# 03-MCU.net
KiCad netlist of a schematic drawn in Altium Designer
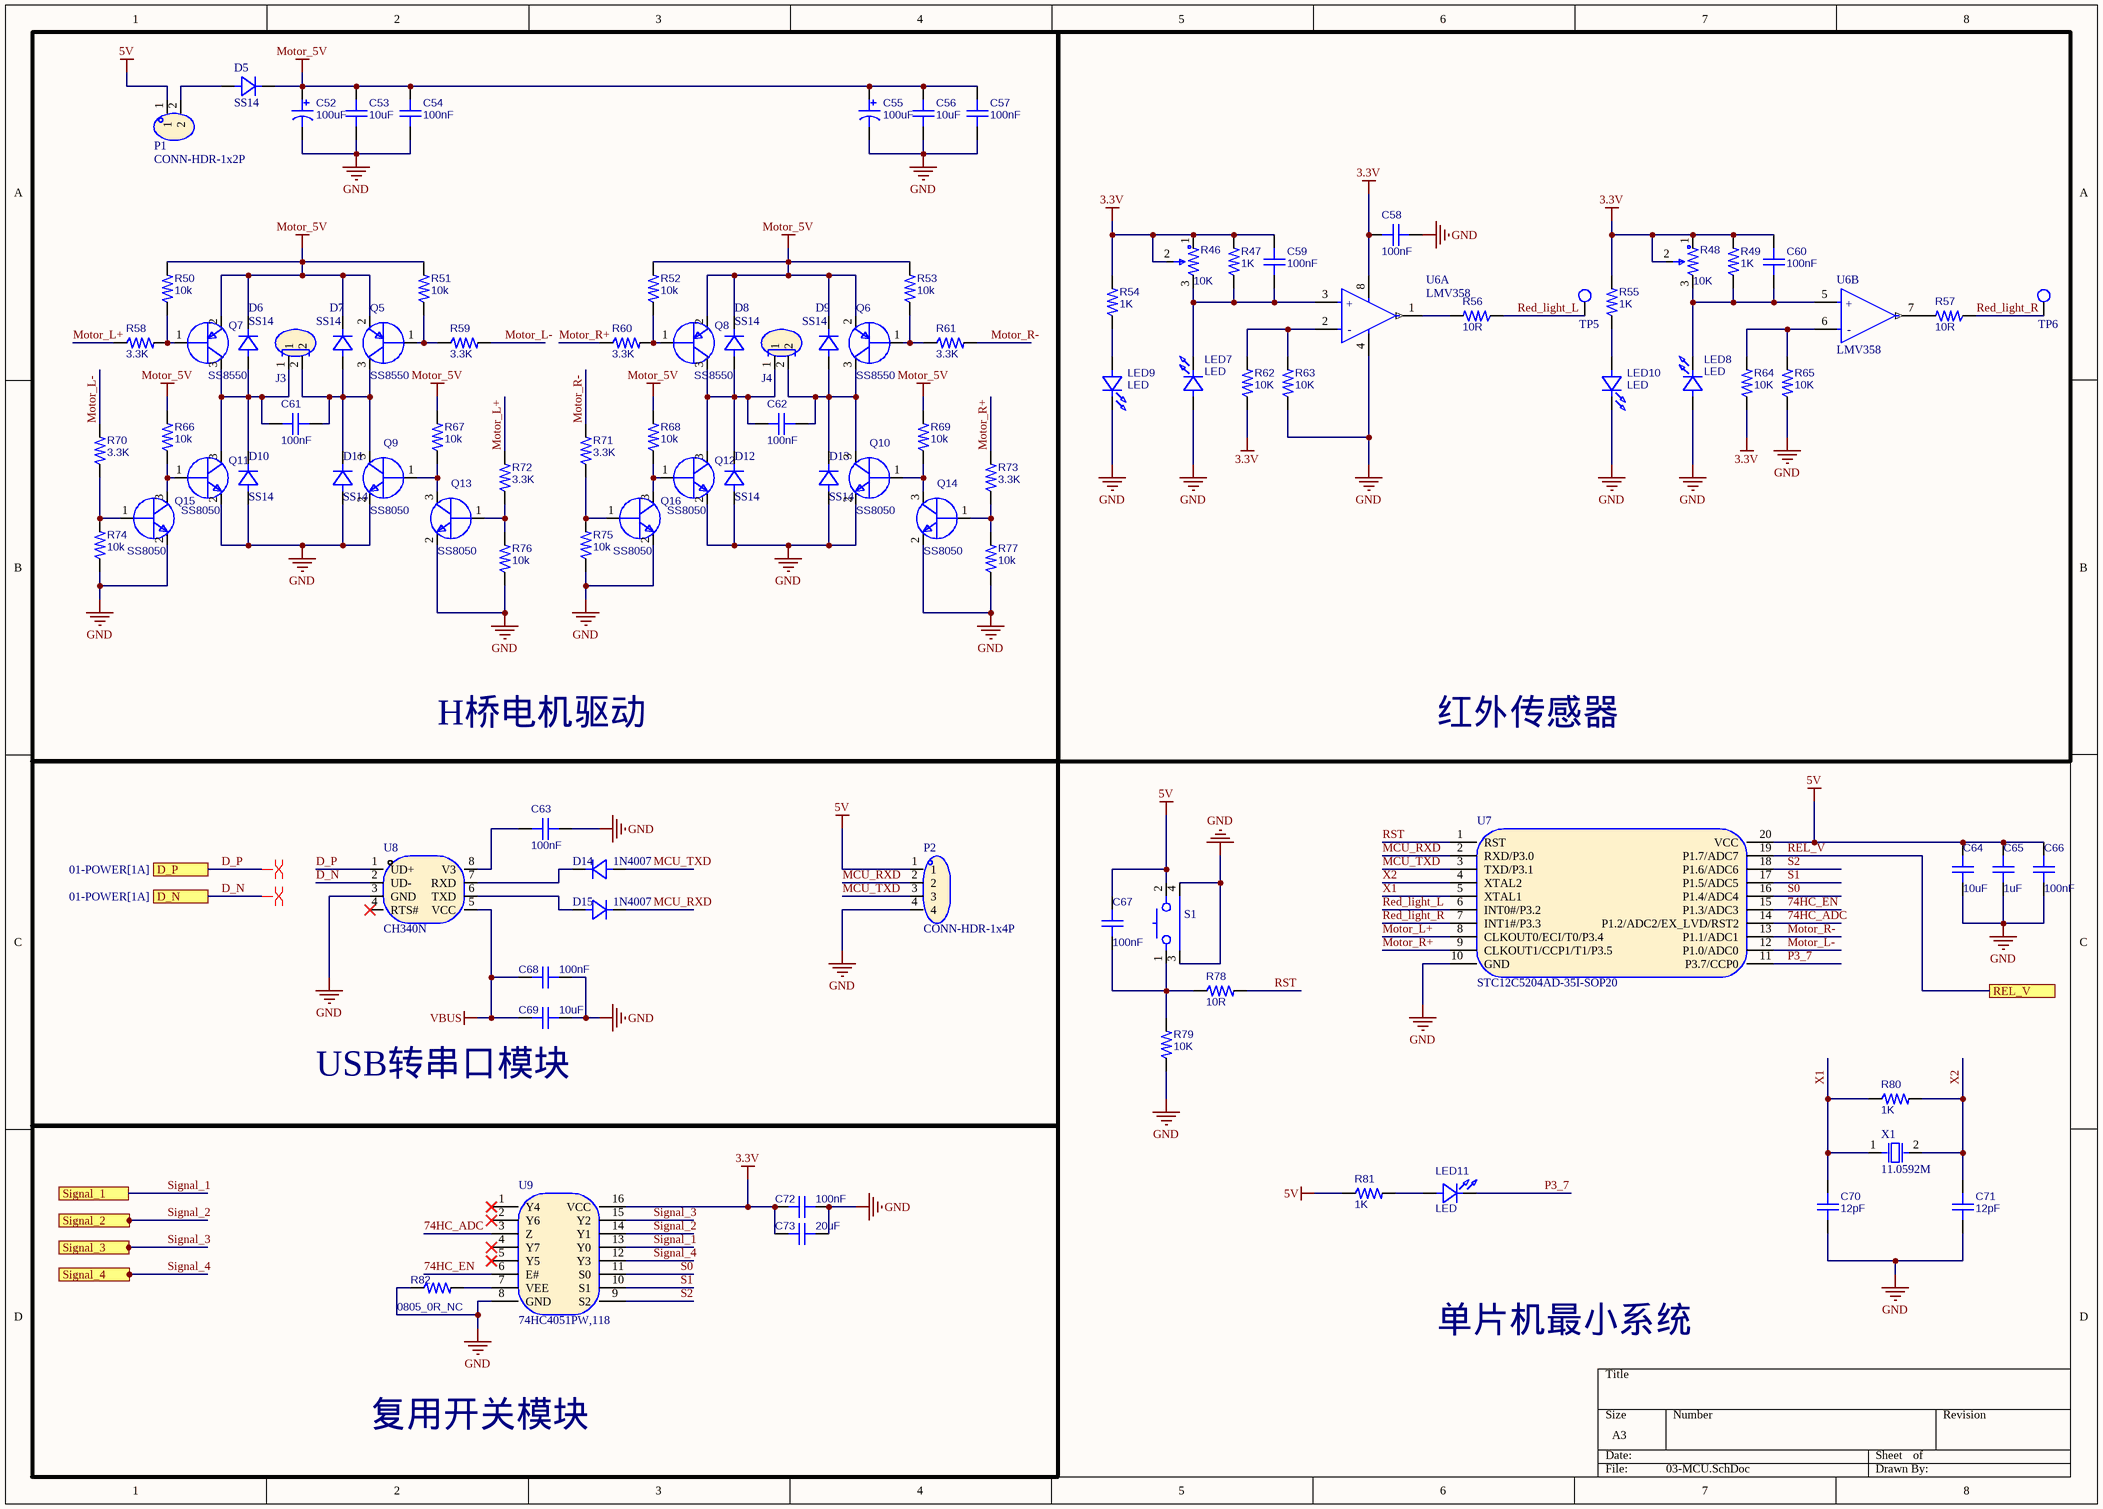
[diagram p0: 03-MCU.SchDoc]

(export (version "E")
  (design (tool "Eeschema 10.0.6"))
  (components
    (comp (ref "C52")
      (value "100uF")
      (footprint "CAPA-TH-5020-P2.0")
      (description "电解电容")
      (fields
        (field (name "BOM_MANUFACTURER PART") "普通黑色470UF 50V")
        (field (name "BOM_SUPPLIER PART") "C34642")
      )
      (libsource (lib "声源跟踪小车原理图库") (part "CAPA"))
    )
    (comp (ref "C53")
      (value "10uF")
      (footprint "CAP-SMD-0603")
      (description "贴片电容")
      (fields
        (field (name "BOM_MANUFACTURER PART") "CL03A104KQ3NNNC")
        (field (name "BOM_SUPPLIER PART") "C160831")
        (field (name "CONTRIBUTOR") "LCSC")
      )
      (libsource (lib "声源跟踪小车原理图库") (part "CAP"))
    )
    (comp (ref "C54")
      (value "100nF")
      (footprint "CAP-SMD-0603")
      (description "贴片电容")
      (fields
        (field (name "BOM_MANUFACTURER PART") "CL03A104KQ3NNNC")
        (field (name "BOM_SUPPLIER PART") "C160831")
        (field (name "CONTRIBUTOR") "LCSC")
      )
      (libsource (lib "声源跟踪小车原理图库") (part "CAP"))
    )
    (comp (ref "C55")
      (value "100uF")
      (footprint "CAPA-TH-5020-P2.0")
      (description "电解电容")
      (fields
        (field (name "BOM_MANUFACTURER PART") "普通黑色470UF 50V")
        (field (name "BOM_SUPPLIER PART") "C34642")
      )
      (libsource (lib "声源跟踪小车原理图库") (part "CAPA"))
    )
    (comp (ref "C56")
      (value "10uF")
      (footprint "CAP-SMD-0603")
      (description "贴片电容")
      (fields
        (field (name "BOM_MANUFACTURER PART") "CL03A104KQ3NNNC")
        (field (name "BOM_SUPPLIER PART") "C160831")
        (field (name "CONTRIBUTOR") "LCSC")
      )
      (libsource (lib "声源跟踪小车原理图库") (part "CAP"))
    )
    (comp (ref "C57")
      (value "100nF")
      (footprint "CAP-SMD-0603")
      (description "贴片电容")
      (fields
        (field (name "BOM_MANUFACTURER PART") "CL03A104KQ3NNNC")
        (field (name "BOM_SUPPLIER PART") "C160831")
        (field (name "CONTRIBUTOR") "LCSC")
      )
      (libsource (lib "声源跟踪小车原理图库") (part "CAP"))
    )
    (comp (ref "C58")
      (value "100nF")
      (footprint "CAP-SMD-0603")
      (description "贴片电容")
      (fields
        (field (name "BOM_MANUFACTURER PART") "CL03A104KQ3NNNC")
        (field (name "BOM_SUPPLIER PART") "C160831")
        (field (name "CONTRIBUTOR") "LCSC")
      )
      (libsource (lib "声源跟踪小车原理图库") (part "CAP"))
    )
    (comp (ref "C59")
      (value "100nF")
      (footprint "CAP-SMD-0603")
      (description "贴片电容")
      (fields
        (field (name "BOM_MANUFACTURER PART") "CL03A104KQ3NNNC")
        (field (name "BOM_SUPPLIER PART") "C160831")
        (field (name "CONTRIBUTOR") "LCSC")
      )
      (libsource (lib "声源跟踪小车原理图库") (part "CAP"))
    )
    (comp (ref "C60")
      (value "100nF")
      (footprint "CAP-SMD-0603")
      (description "贴片电容")
      (fields
        (field (name "BOM_MANUFACTURER PART") "CL03A104KQ3NNNC")
        (field (name "BOM_SUPPLIER PART") "C160831")
        (field (name "CONTRIBUTOR") "LCSC")
      )
      (libsource (lib "声源跟踪小车原理图库") (part "CAP"))
    )
    (comp (ref "C61")
      (value "100nF")
      (footprint "CAP-SMD-0603")
      (description "贴片电容")
      (fields
        (field (name "BOM_MANUFACTURER PART") "CL03A104KQ3NNNC")
        (field (name "BOM_SUPPLIER PART") "C160831")
        (field (name "CONTRIBUTOR") "LCSC")
      )
      (libsource (lib "声源跟踪小车原理图库") (part "CAP"))
    )
    (comp (ref "C62")
      (value "100nF")
      (footprint "CAP-SMD-0603")
      (description "贴片电容")
      (fields
        (field (name "BOM_MANUFACTURER PART") "CL03A104KQ3NNNC")
        (field (name "BOM_SUPPLIER PART") "C160831")
        (field (name "CONTRIBUTOR") "LCSC")
      )
      (libsource (lib "声源跟踪小车原理图库") (part "CAP"))
    )
    (comp (ref "C63")
      (value "100nF")
      (footprint "CAP-SMD-0603")
      (description "贴片电容")
      (fields
        (field (name "BOM_MANUFACTURER PART") "CL03A104KQ3NNNC")
        (field (name "BOM_SUPPLIER PART") "C160831")
        (field (name "CONTRIBUTOR") "LCSC")
      )
      (libsource (lib "声源跟踪小车原理图库") (part "CAP"))
    )
    (comp (ref "C64")
      (value "10uF")
      (footprint "CAP-SMD-0603")
      (description "贴片电容")
      (fields
        (field (name "BOM_MANUFACTURER PART") "CL03A104KQ3NNNC")
        (field (name "BOM_SUPPLIER PART") "C160831")
        (field (name "CONTRIBUTOR") "LCSC")
      )
      (libsource (lib "声源跟踪小车原理图库") (part "CAP"))
    )
    (comp (ref "C65")
      (value "1uF")
      (footprint "CAP-SMD-0603")
      (description "贴片电容")
      (fields
        (field (name "BOM_MANUFACTURER PART") "CL03A104KQ3NNNC")
        (field (name "BOM_SUPPLIER PART") "C160831")
        (field (name "CONTRIBUTOR") "LCSC")
      )
      (libsource (lib "声源跟踪小车原理图库") (part "CAP"))
    )
    (comp (ref "C66")
      (value "100nF")
      (footprint "CAP-SMD-0603")
      (description "贴片电容")
      (fields
        (field (name "BOM_MANUFACTURER PART") "CL03A104KQ3NNNC")
        (field (name "BOM_SUPPLIER PART") "C160831")
        (field (name "CONTRIBUTOR") "LCSC")
      )
      (libsource (lib "声源跟踪小车原理图库") (part "CAP"))
    )
    (comp (ref "C67")
      (value "100nF")
      (footprint "CAP-SMD-0603")
      (description "贴片电容")
      (fields
        (field (name "BOM_MANUFACTURER PART") "CL03A104KQ3NNNC")
        (field (name "BOM_SUPPLIER PART") "C160831")
        (field (name "CONTRIBUTOR") "LCSC")
      )
      (libsource (lib "声源跟踪小车原理图库") (part "CAP"))
    )
    (comp (ref "C68")
      (value "100nF")
      (footprint "CAP-SMD-0603")
      (description "贴片电容")
      (fields
        (field (name "BOM_MANUFACTURER PART") "CL03A104KQ3NNNC")
        (field (name "BOM_SUPPLIER PART") "C160831")
        (field (name "CONTRIBUTOR") "LCSC")
      )
      (libsource (lib "声源跟踪小车原理图库") (part "CAP"))
    )
    (comp (ref "C69")
      (value "10uF")
      (footprint "CAP-SMD-0603")
      (description "贴片电容")
      (fields
        (field (name "BOM_MANUFACTURER PART") "CL03A104KQ3NNNC")
        (field (name "BOM_SUPPLIER PART") "C160831")
        (field (name "CONTRIBUTOR") "LCSC")
      )
      (libsource (lib "声源跟踪小车原理图库") (part "CAP"))
    )
    (comp (ref "C70")
      (value "12pF")
      (footprint "CAP-SMD-0603")
      (description "贴片电容")
      (fields
        (field (name "BOM_MANUFACTURER PART") "CL03A104KQ3NNNC")
        (field (name "BOM_SUPPLIER PART") "C160831")
        (field (name "CONTRIBUTOR") "LCSC")
      )
      (libsource (lib "声源跟踪小车原理图库") (part "CAP"))
    )
    (comp (ref "C71")
      (value "12pF")
      (footprint "CAP-SMD-0603")
      (description "贴片电容")
      (fields
        (field (name "BOM_MANUFACTURER PART") "CL03A104KQ3NNNC")
        (field (name "BOM_SUPPLIER PART") "C160831")
        (field (name "CONTRIBUTOR") "LCSC")
      )
      (libsource (lib "声源跟踪小车原理图库") (part "CAP"))
    )
    (comp (ref "C72")
      (value "100nF")
      (footprint "CAP-SMD-0603")
      (description "贴片电容")
      (fields
        (field (name "BOM_MANUFACTURER PART") "CL03A104KQ3NNNC")
        (field (name "BOM_SUPPLIER PART") "C160831")
        (field (name "CONTRIBUTOR") "LCSC")
      )
      (libsource (lib "声源跟踪小车原理图库") (part "CAP"))
    )
    (comp (ref "C73")
      (value "20uF")
      (footprint "CAP-SMD-0603")
      (description "贴片电容")
      (fields
        (field (name "BOM_MANUFACTURER PART") "CL03A104KQ3NNNC")
        (field (name "BOM_SUPPLIER PART") "C160831")
        (field (name "CONTRIBUTOR") "LCSC")
      )
      (libsource (lib "声源跟踪小车原理图库") (part "CAP"))
    )
    (comp (ref "D5")
      (value "SS14")
      (footprint "SOD-123-P3.4")
      (description "二极管1N4148W")
      (fields (field (name "MANUFACTURER") "PSI(宝力芯)") (field (name "MANUFACTURER PART") "1N4148W"))
      (libsource (lib "声源跟踪小车原理图库") (part "Diode"))
    )
    (comp (ref "D6")
      (value "SS14")
      (footprint "SOD-123-P3.4")
      (description "二极管1N4148W")
      (fields (field (name "MANUFACTURER") "PSI(宝力芯)") (field (name "MANUFACTURER PART") "1N4148W"))
      (libsource (lib "声源跟踪小车原理图库") (part "Diode"))
    )
    (comp (ref "D7")
      (value "SS14")
      (footprint "SOD-123-P3.4")
      (description "二极管1N4148W")
      (fields (field (name "MANUFACTURER") "PSI(宝力芯)") (field (name "MANUFACTURER PART") "1N4148W"))
      (libsource (lib "声源跟踪小车原理图库") (part "Diode"))
    )
    (comp (ref "D8")
      (value "SS14")
      (footprint "SOD-123-P3.4")
      (description "二极管1N4148W")
      (fields (field (name "MANUFACTURER") "PSI(宝力芯)") (field (name "MANUFACTURER PART") "1N4148W"))
      (libsource (lib "声源跟踪小车原理图库") (part "Diode"))
    )
    (comp (ref "D9")
      (value "SS14")
      (footprint "SOD-123-P3.4")
      (description "二极管1N4148W")
      (fields (field (name "MANUFACTURER") "PSI(宝力芯)") (field (name "MANUFACTURER PART") "1N4148W"))
      (libsource (lib "声源跟踪小车原理图库") (part "Diode"))
    )
    (comp (ref "D10")
      (value "SS14")
      (footprint "SOD-123-P3.4")
      (description "二极管1N4148W")
      (fields (field (name "MANUFACTURER") "PSI(宝力芯)") (field (name "MANUFACTURER PART") "1N4148W"))
      (libsource (lib "声源跟踪小车原理图库") (part "Diode"))
    )
    (comp (ref "D11")
      (value "SS14")
      (footprint "SOD-123-P3.4")
      (description "二极管1N4148W")
      (fields (field (name "MANUFACTURER") "PSI(宝力芯)") (field (name "MANUFACTURER PART") "1N4148W"))
      (libsource (lib "声源跟踪小车原理图库") (part "Diode"))
    )
    (comp (ref "D12")
      (value "SS14")
      (footprint "SOD-123-P3.4")
      (description "二极管1N4148W")
      (fields (field (name "MANUFACTURER") "PSI(宝力芯)") (field (name "MANUFACTURER PART") "1N4148W"))
      (libsource (lib "声源跟踪小车原理图库") (part "Diode"))
    )
    (comp (ref "D13")
      (value "SS14")
      (footprint "SOD-123-P3.4")
      (description "二极管1N4148W")
      (fields (field (name "MANUFACTURER") "PSI(宝力芯)") (field (name "MANUFACTURER PART") "1N4148W"))
      (libsource (lib "声源跟踪小车原理图库") (part "Diode"))
    )
    (comp (ref "D14")
      (value "1N4007")
      (footprint "SOD-123-P3.4")
      (description "二极管1N4148W")
      (fields (field (name "MANUFACTURER") "PSI(宝力芯)") (field (name "MANUFACTURER PART") "1N4148W"))
      (libsource (lib "声源跟踪小车原理图库") (part "Diode"))
    )
    (comp (ref "D15")
      (value "1N4007")
      (footprint "SOD-123-P3.4")
      (description "二极管1N4148W")
      (fields (field (name "MANUFACTURER") "PSI(宝力芯)") (field (name "MANUFACTURER PART") "1N4148W"))
      (libsource (lib "声源跟踪小车原理图库") (part "Diode"))
    )
    (comp (ref "J3")
      (value "CONN-2P")
      (footprint "CONN-TH-CDS-1x2P-P2.54")
      (description "连接插座2pin")
      (fields (field (name "MANUFACTURER") "KEFA(科发)") (field (name "MANUFACTURER PART") "KF301-5.0-2P"))
      (libsource (lib "声源跟踪小车原理图库") (part "CONN-2P"))
    )
    (comp (ref "J4")
      (value "CONN-2P")
      (footprint "CONN-TH-CDS-1x2P-P2.54")
      (description "连接插座2pin")
      (fields (field (name "MANUFACTURER") "KEFA(科发)") (field (name "MANUFACTURER PART") "KF301-5.0-2P"))
      (libsource (lib "声源跟踪小车原理图库") (part "CONN-2P"))
    )
    (comp (ref "LED7")
      (value "LED")
      (footprint "LED-TH-D5.0-P2.54")
      (description "LED灯,发光二极管")
      (fields
        (field (name "BOM_SUPPLIER PART") "C434447")
        (field (name "BOM_MANUFACTURER PART") "SZYY0402B")
        (field (name "CONTRIBUTOR") "LCSC")
      )
      (libsource (lib "声源跟踪小车原理图库") (part "LED"))
    )
    (comp (ref "LED8")
      (value "LED")
      (footprint "LED-TH-D5.0-P2.54")
      (description "LED灯,发光二极管")
      (fields
        (field (name "BOM_SUPPLIER PART") "C434447")
        (field (name "BOM_MANUFACTURER PART") "SZYY0402B")
        (field (name "CONTRIBUTOR") "LCSC")
      )
      (libsource (lib "声源跟踪小车原理图库") (part "LED"))
    )
    (comp (ref "LED9")
      (value "LED")
      (footprint "LED-TH-D5.0-P2.54")
      (description "LED灯,发光二极管")
      (fields
        (field (name "BOM_SUPPLIER PART") "C434447")
        (field (name "BOM_MANUFACTURER PART") "SZYY0402B")
        (field (name "CONTRIBUTOR") "LCSC")
      )
      (libsource (lib "声源跟踪小车原理图库") (part "LED"))
    )
    (comp (ref "LED10")
      (value "LED")
      (footprint "LED-TH-D5.0-P2.54")
      (description "LED灯,发光二极管")
      (fields
        (field (name "BOM_SUPPLIER PART") "C434447")
        (field (name "BOM_MANUFACTURER PART") "SZYY0402B")
        (field (name "CONTRIBUTOR") "LCSC")
      )
      (libsource (lib "声源跟踪小车原理图库") (part "LED"))
    )
    (comp (ref "LED11")
      (value "LED")
      (footprint "LED-SMD-0805")
      (description "LED灯,发光二极管")
      (fields
        (field (name "BOM_SUPPLIER PART") "C434447")
        (field (name "BOM_MANUFACTURER PART") "SZYY0402B")
        (field (name "CONTRIBUTOR") "LCSC")
      )
      (libsource (lib "声源跟踪小车原理图库") (part "LED"))
    )
    (comp (ref "P1")
      (value "CONN-HDR-1x2P")
      (footprint "CONN-TH-1X2P-P2.54")
      (description "排针1*2pin")
      (fields
        (field (name "MANUFACTURER") "kinghelm(金航标)")
        (field (name "MANUFACTURER PART") "KH-2.54PH180-1X2P-L11.5")
      )
      (libsource (lib "声源跟踪小车原理图库") (part "CONN-HDR-1x2P"))
    )
    (comp (ref "P2")
      (value "CONN-HDR-1x4P")
      (footprint "CONN-TH-1X4P-P2.54")
      (description "排针1*4pin")
      (fields
        (field (name "MANUFACTURER") "Wcon(维峰电子)")
        (field (name "MANUFACTURER PART") "1125-1104G0S116C001")
      )
      (libsource (lib "声源跟踪小车原理图库") (part "CONN-HDR-1x4P"))
    )
    (comp (ref "Q5")
      (value "SS8550")
      (footprint "SOT-23-3-LP2.28-P1.91")
      (description "贴片PNP三极管")
      (fields
        (field (name "BOM_SUPPLIER PART") "C2891799")
        (field (name "BOM_MANUFACTURER PART") "S9012")
        (field (name "CONTRIBUTOR") "LCSC")
      )
      (libsource (lib "声源跟踪小车原理图库") (part "PNP-SOT-23-3"))
    )
    (comp (ref "Q6")
      (value "SS8550")
      (footprint "SOT-23-3-LP2.28-P1.91")
      (description "贴片PNP三极管")
      (fields
        (field (name "BOM_SUPPLIER PART") "C2891799")
        (field (name "BOM_MANUFACTURER PART") "S9012")
        (field (name "CONTRIBUTOR") "LCSC")
      )
      (libsource (lib "声源跟踪小车原理图库") (part "PNP-SOT-23-3"))
    )
    (comp (ref "Q7")
      (value "SS8550")
      (footprint "SOT-23-3-LP2.28-P1.91")
      (description "贴片PNP三极管")
      (fields
        (field (name "BOM_SUPPLIER PART") "C2891799")
        (field (name "BOM_MANUFACTURER PART") "S9012")
        (field (name "CONTRIBUTOR") "LCSC")
      )
      (libsource (lib "声源跟踪小车原理图库") (part "PNP-SOT-23-3"))
    )
    (comp (ref "Q8")
      (value "SS8550")
      (footprint "SOT-23-3-LP2.28-P1.91")
      (description "贴片PNP三极管")
      (fields
        (field (name "BOM_SUPPLIER PART") "C2891799")
        (field (name "BOM_MANUFACTURER PART") "S9012")
        (field (name "CONTRIBUTOR") "LCSC")
      )
      (libsource (lib "声源跟踪小车原理图库") (part "PNP-SOT-23-3"))
    )
    (comp (ref "Q9")
      (value "SS8050")
      (footprint "SOT-23-3-LP2.28-P1.91")
      (description "贴片NPN三极管")
      (fields
        (field (name "BOM_SUPPLIER PART") "C2898668")
        (field (name "BOM_MANUFACTURER PART") "S9013")
        (field (name "CONTRIBUTOR") "LCSC")
      )
      (libsource (lib "声源跟踪小车原理图库") (part "NPN-SOT-23-3"))
    )
    (comp (ref "Q10")
      (value "SS8050")
      (footprint "SOT-23-3-LP2.28-P1.91")
      (description "贴片NPN三极管")
      (fields
        (field (name "BOM_SUPPLIER PART") "C2898668")
        (field (name "BOM_MANUFACTURER PART") "S9013")
        (field (name "CONTRIBUTOR") "LCSC")
      )
      (libsource (lib "声源跟踪小车原理图库") (part "NPN-SOT-23-3"))
    )
    (comp (ref "Q11")
      (value "SS8050")
      (footprint "SOT-23-3-LP2.28-P1.91")
      (description "贴片NPN三极管")
      (fields
        (field (name "BOM_SUPPLIER PART") "C2898668")
        (field (name "BOM_MANUFACTURER PART") "S9013")
        (field (name "CONTRIBUTOR") "LCSC")
      )
      (libsource (lib "声源跟踪小车原理图库") (part "NPN-SOT-23-3"))
    )
    (comp (ref "Q12")
      (value "SS8050")
      (footprint "SOT-23-3-LP2.28-P1.91")
      (description "贴片NPN三极管")
      (fields
        (field (name "BOM_SUPPLIER PART") "C2898668")
        (field (name "BOM_MANUFACTURER PART") "S9013")
        (field (name "CONTRIBUTOR") "LCSC")
      )
      (libsource (lib "声源跟踪小车原理图库") (part "NPN-SOT-23-3"))
    )
    (comp (ref "Q13")
      (value "SS8050")
      (footprint "SOT-23-3-LP2.28-P1.91")
      (description "贴片NPN三极管")
      (fields
        (field (name "BOM_SUPPLIER PART") "C2898668")
        (field (name "BOM_MANUFACTURER PART") "S9013")
        (field (name "CONTRIBUTOR") "LCSC")
      )
      (libsource (lib "声源跟踪小车原理图库") (part "NPN-SOT-23-3"))
    )
    (comp (ref "Q14")
      (value "SS8050")
      (footprint "SOT-23-3-LP2.28-P1.91")
      (description "贴片NPN三极管")
      (fields
        (field (name "BOM_SUPPLIER PART") "C2898668")
        (field (name "BOM_MANUFACTURER PART") "S9013")
        (field (name "CONTRIBUTOR") "LCSC")
      )
      (libsource (lib "声源跟踪小车原理图库") (part "NPN-SOT-23-3"))
    )
    (comp (ref "Q15")
      (value "SS8050")
      (footprint "SOT-23-3-LP2.28-P1.91")
      (description "贴片NPN三极管")
      (fields
        (field (name "BOM_SUPPLIER PART") "C2898668")
        (field (name "BOM_MANUFACTURER PART") "S9013")
        (field (name "CONTRIBUTOR") "LCSC")
      )
      (libsource (lib "声源跟踪小车原理图库") (part "NPN-SOT-23-3"))
    )
    (comp (ref "Q16")
      (value "SS8050")
      (footprint "SOT-23-3-LP2.28-P1.91")
      (description "贴片NPN三极管")
      (fields
        (field (name "BOM_SUPPLIER PART") "C2898668")
        (field (name "BOM_MANUFACTURER PART") "S9013")
        (field (name "CONTRIBUTOR") "LCSC")
      )
      (libsource (lib "声源跟踪小车原理图库") (part "NPN-SOT-23-3"))
    )
    (comp (ref "R46")
      (value "10K")
      (footprint "RES-TH-ADJ-3396W")
      (description "可调电阻,电位器")
      (fields
        (field (name "BOM_SUPPLIER PART") "C118966")
        (field (name "BOM_MANUFACTURER PART") "3362P-1-104")
        (field (name "CONTRIBUTOR") "LCSC")
      )
      (libsource (lib "声源跟踪小车原理图库") (part "RES-ADJ"))
    )
    (comp (ref "R47")
      (value "1K")
      (footprint "RES-SMD-0603")
      (description "贴片电阻")
      (fields
        (field (name "BOM_SUPPLIER PART") "C118966")
        (field (name "BOM_MANUFACTURER PART") "3362P-1-104")
        (field (name "CONTRIBUTOR") "LCSC")
      )
      (libsource (lib "声源跟踪小车原理图库") (part "RES"))
    )
    (comp (ref "R48")
      (value "10K")
      (footprint "RES-TH-ADJ-3396W")
      (description "可调电阻,电位器")
      (fields
        (field (name "BOM_SUPPLIER PART") "C118966")
        (field (name "BOM_MANUFACTURER PART") "3362P-1-104")
        (field (name "CONTRIBUTOR") "LCSC")
      )
      (libsource (lib "声源跟踪小车原理图库") (part "RES-ADJ"))
    )
    (comp (ref "R49")
      (value "1K")
      (footprint "RES-SMD-0603")
      (description "贴片电阻")
      (fields
        (field (name "BOM_SUPPLIER PART") "C118966")
        (field (name "BOM_MANUFACTURER PART") "3362P-1-104")
        (field (name "CONTRIBUTOR") "LCSC")
      )
      (libsource (lib "声源跟踪小车原理图库") (part "RES"))
    )
    (comp (ref "R50")
      (value "10k")
      (footprint "RES-SMD-0603")
      (description "贴片电阻")
      (fields
        (field (name "BOM_SUPPLIER PART") "C118966")
        (field (name "BOM_MANUFACTURER PART") "3362P-1-104")
        (field (name "CONTRIBUTOR") "LCSC")
      )
      (libsource (lib "声源跟踪小车原理图库") (part "RES"))
    )
    (comp (ref "R51")
      (value "10k")
      (footprint "RES-SMD-0603")
      (description "贴片电阻")
      (fields
        (field (name "BOM_SUPPLIER PART") "C118966")
        (field (name "BOM_MANUFACTURER PART") "3362P-1-104")
        (field (name "CONTRIBUTOR") "LCSC")
      )
      (libsource (lib "声源跟踪小车原理图库") (part "RES"))
    )
    (comp (ref "R52")
      (value "10k")
      (footprint "RES-SMD-0603")
      (description "贴片电阻")
      (fields
        (field (name "BOM_SUPPLIER PART") "C118966")
        (field (name "BOM_MANUFACTURER PART") "3362P-1-104")
        (field (name "CONTRIBUTOR") "LCSC")
      )
      (libsource (lib "声源跟踪小车原理图库") (part "RES"))
    )
    (comp (ref "R53")
      (value "10k")
      (footprint "RES-SMD-0603")
      (description "贴片电阻")
      (fields
        (field (name "BOM_SUPPLIER PART") "C118966")
        (field (name "BOM_MANUFACTURER PART") "3362P-1-104")
        (field (name "CONTRIBUTOR") "LCSC")
      )
      (libsource (lib "声源跟踪小车原理图库") (part "RES"))
    )
    (comp (ref "R54")
      (value "1K")
      (footprint "RES-SMD-0603")
      (description "贴片电阻")
      (fields
        (field (name "BOM_SUPPLIER PART") "C118966")
        (field (name "BOM_MANUFACTURER PART") "3362P-1-104")
        (field (name "CONTRIBUTOR") "LCSC")
      )
      (libsource (lib "声源跟踪小车原理图库") (part "RES"))
    )
    (comp (ref "R55")
      (value "1K")
      (footprint "RES-SMD-0603")
      (description "贴片电阻")
      (fields
        (field (name "BOM_SUPPLIER PART") "C118966")
        (field (name "BOM_MANUFACTURER PART") "3362P-1-104")
        (field (name "CONTRIBUTOR") "LCSC")
      )
      (libsource (lib "声源跟踪小车原理图库") (part "RES"))
    )
    (comp (ref "R56")
      (value "10R")
      (footprint "RES-SMD-0603")
      (description "贴片电阻")
      (fields
        (field (name "BOM_SUPPLIER PART") "C118966")
        (field (name "BOM_MANUFACTURER PART") "3362P-1-104")
        (field (name "CONTRIBUTOR") "LCSC")
      )
      (libsource (lib "声源跟踪小车原理图库") (part "RES"))
    )
    (comp (ref "R57")
      (value "10R")
      (footprint "RES-SMD-0603")
      (description "贴片电阻")
      (fields
        (field (name "BOM_SUPPLIER PART") "C118966")
        (field (name "BOM_MANUFACTURER PART") "3362P-1-104")
        (field (name "CONTRIBUTOR") "LCSC")
      )
      (libsource (lib "声源跟踪小车原理图库") (part "RES"))
    )
    (comp (ref "R58")
      (value "3.3K")
      (footprint "RES-SMD-0603")
      (description "贴片电阻")
      (fields
        (field (name "BOM_SUPPLIER PART") "C118966")
        (field (name "BOM_MANUFACTURER PART") "3362P-1-104")
        (field (name "CONTRIBUTOR") "LCSC")
      )
      (libsource (lib "声源跟踪小车原理图库") (part "RES"))
    )
    (comp (ref "R59")
      (value "3.3K")
      (footprint "RES-SMD-0603")
      (description "贴片电阻")
      (fields
        (field (name "BOM_SUPPLIER PART") "C118966")
        (field (name "BOM_MANUFACTURER PART") "3362P-1-104")
        (field (name "CONTRIBUTOR") "LCSC")
      )
      (libsource (lib "声源跟踪小车原理图库") (part "RES"))
    )
    (comp (ref "R60")
      (value "3.3K")
      (footprint "RES-SMD-0603")
      (description "贴片电阻")
      (fields
        (field (name "BOM_SUPPLIER PART") "C118966")
        (field (name "BOM_MANUFACTURER PART") "3362P-1-104")
        (field (name "CONTRIBUTOR") "LCSC")
      )
      (libsource (lib "声源跟踪小车原理图库") (part "RES"))
    )
    (comp (ref "R61")
      (value "3.3K")
      (footprint "RES-SMD-0603")
      (description "贴片电阻")
      (fields
        (field (name "BOM_SUPPLIER PART") "C118966")
        (field (name "BOM_MANUFACTURER PART") "3362P-1-104")
        (field (name "CONTRIBUTOR") "LCSC")
      )
      (libsource (lib "声源跟踪小车原理图库") (part "RES"))
    )
    (comp (ref "R62")
      (value "10K")
      (footprint "RES-SMD-0603")
      (description "贴片电阻")
      (fields
        (field (name "BOM_SUPPLIER PART") "C118966")
        (field (name "BOM_MANUFACTURER PART") "3362P-1-104")
        (field (name "CONTRIBUTOR") "LCSC")
      )
      (libsource (lib "声源跟踪小车原理图库") (part "RES"))
    )
    (comp (ref "R63")
      (value "10K")
      (footprint "RES-SMD-0603")
      (description "贴片电阻")
      (fields
        (field (name "BOM_SUPPLIER PART") "C118966")
        (field (name "BOM_MANUFACTURER PART") "3362P-1-104")
        (field (name "CONTRIBUTOR") "LCSC")
      )
      (libsource (lib "声源跟踪小车原理图库") (part "RES"))
    )
    (comp (ref "R64")
      (value "10K")
      (footprint "RES-SMD-0603")
      (description "贴片电阻")
      (fields
        (field (name "BOM_SUPPLIER PART") "C118966")
        (field (name "BOM_MANUFACTURER PART") "3362P-1-104")
        (field (name "CONTRIBUTOR") "LCSC")
      )
      (libsource (lib "声源跟踪小车原理图库") (part "RES"))
    )
    (comp (ref "R65")
      (value "10K")
      (footprint "RES-SMD-0603")
      (description "贴片电阻")
      (fields
        (field (name "BOM_SUPPLIER PART") "C118966")
        (field (name "BOM_MANUFACTURER PART") "3362P-1-104")
        (field (name "CONTRIBUTOR") "LCSC")
      )
      (libsource (lib "声源跟踪小车原理图库") (part "RES"))
    )
    (comp (ref "R66")
      (value "10k")
      (footprint "RES-SMD-0603")
      (description "贴片电阻")
      (fields
        (field (name "BOM_SUPPLIER PART") "C118966")
        (field (name "BOM_MANUFACTURER PART") "3362P-1-104")
        (field (name "CONTRIBUTOR") "LCSC")
      )
      (libsource (lib "声源跟踪小车原理图库") (part "RES"))
    )
    (comp (ref "R67")
      (value "10k")
      (footprint "RES-SMD-0603")
      (description "贴片电阻")
      (fields
        (field (name "BOM_SUPPLIER PART") "C118966")
        (field (name "BOM_MANUFACTURER PART") "3362P-1-104")
        (field (name "CONTRIBUTOR") "LCSC")
      )
      (libsource (lib "声源跟踪小车原理图库") (part "RES"))
    )
    (comp (ref "R68")
      (value "10k")
      (footprint "RES-SMD-0603")
      (description "贴片电阻")
      (fields
        (field (name "BOM_SUPPLIER PART") "C118966")
        (field (name "BOM_MANUFACTURER PART") "3362P-1-104")
        (field (name "CONTRIBUTOR") "LCSC")
      )
      (libsource (lib "声源跟踪小车原理图库") (part "RES"))
    )
    (comp (ref "R69")
      (value "10k")
      (footprint "RES-SMD-0603")
      (description "贴片电阻")
      (fields
        (field (name "BOM_SUPPLIER PART") "C118966")
        (field (name "BOM_MANUFACTURER PART") "3362P-1-104")
        (field (name "CONTRIBUTOR") "LCSC")
      )
      (libsource (lib "声源跟踪小车原理图库") (part "RES"))
    )
    (comp (ref "R70")
      (value "3.3K")
      (footprint "RES-SMD-0603")
      (description "贴片电阻")
      (fields
        (field (name "BOM_SUPPLIER PART") "C118966")
        (field (name "BOM_MANUFACTURER PART") "3362P-1-104")
        (field (name "CONTRIBUTOR") "LCSC")
      )
      (libsource (lib "声源跟踪小车原理图库") (part "RES"))
    )
    (comp (ref "R71")
      (value "3.3K")
      (footprint "RES-SMD-0603")
      (description "贴片电阻")
      (fields
        (field (name "BOM_SUPPLIER PART") "C118966")
        (field (name "BOM_MANUFACTURER PART") "3362P-1-104")
        (field (name "CONTRIBUTOR") "LCSC")
      )
      (libsource (lib "声源跟踪小车原理图库") (part "RES"))
    )
    (comp (ref "R72")
      (value "3.3K")
      (footprint "RES-SMD-0603")
      (description "贴片电阻")
      (fields
        (field (name "BOM_SUPPLIER PART") "C118966")
        (field (name "BOM_MANUFACTURER PART") "3362P-1-104")
        (field (name "CONTRIBUTOR") "LCSC")
      )
      (libsource (lib "声源跟踪小车原理图库") (part "RES"))
    )
    (comp (ref "R73")
      (value "3.3K")
      (footprint "RES-SMD-0603")
      (description "贴片电阻")
      (fields
        (field (name "BOM_SUPPLIER PART") "C118966")
        (field (name "BOM_MANUFACTURER PART") "3362P-1-104")
        (field (name "CONTRIBUTOR") "LCSC")
      )
      (libsource (lib "声源跟踪小车原理图库") (part "RES"))
    )
    (comp (ref "R74")
      (value "10k")
      (footprint "RES-SMD-0603")
      (description "贴片电阻")
      (fields
        (field (name "BOM_SUPPLIER PART") "C118966")
        (field (name "BOM_MANUFACTURER PART") "3362P-1-104")
        (field (name "CONTRIBUTOR") "LCSC")
      )
      (libsource (lib "声源跟踪小车原理图库") (part "RES"))
    )
    (comp (ref "R75")
      (value "10k")
      (footprint "RES-SMD-0603")
      (description "贴片电阻")
      (fields
        (field (name "BOM_SUPPLIER PART") "C118966")
        (field (name "BOM_MANUFACTURER PART") "3362P-1-104")
        (field (name "CONTRIBUTOR") "LCSC")
      )
      (libsource (lib "声源跟踪小车原理图库") (part "RES"))
    )
    (comp (ref "R76")
      (value "10k")
      (footprint "RES-SMD-0603")
      (description "贴片电阻")
      (fields
        (field (name "BOM_SUPPLIER PART") "C118966")
        (field (name "BOM_MANUFACTURER PART") "3362P-1-104")
        (field (name "CONTRIBUTOR") "LCSC")
      )
      (libsource (lib "声源跟踪小车原理图库") (part "RES"))
    )
    (comp (ref "R77")
      (value "10k")
      (footprint "RES-SMD-0603")
      (description "贴片电阻")
      (fields
        (field (name "BOM_SUPPLIER PART") "C118966")
        (field (name "BOM_MANUFACTURER PART") "3362P-1-104")
        (field (name "CONTRIBUTOR") "LCSC")
      )
      (libsource (lib "声源跟踪小车原理图库") (part "RES"))
    )
    (comp (ref "R78")
      (value "10R")
      (footprint "RES-SMD-0603")
      (description "贴片电阻")
      (fields
        (field (name "BOM_SUPPLIER PART") "C118966")
        (field (name "BOM_MANUFACTURER PART") "3362P-1-104")
        (field (name "CONTRIBUTOR") "LCSC")
      )
      (libsource (lib "声源跟踪小车原理图库") (part "RES"))
    )
    (comp (ref "R79")
      (value "10K")
      (footprint "RES-SMD-0603")
      (description "贴片电阻")
      (fields
        (field (name "BOM_SUPPLIER PART") "C118966")
        (field (name "BOM_MANUFACTURER PART") "3362P-1-104")
        (field (name "CONTRIBUTOR") "LCSC")
      )
      (libsource (lib "声源跟踪小车原理图库") (part "RES"))
    )
    (comp (ref "R80")
      (value "1K")
      (footprint "RES-SMD-0603")
      (description "贴片电阻")
      (fields
        (field (name "BOM_SUPPLIER PART") "C118966")
        (field (name "BOM_MANUFACTURER PART") "3362P-1-104")
        (field (name "CONTRIBUTOR") "LCSC")
      )
      (libsource (lib "声源跟踪小车原理图库") (part "RES"))
    )
    (comp (ref "R81")
      (value "1K")
      (footprint "RES-SMD-0603")
      (description "贴片电阻")
      (fields
        (field (name "BOM_SUPPLIER PART") "C118966")
        (field (name "BOM_MANUFACTURER PART") "3362P-1-104")
        (field (name "CONTRIBUTOR") "LCSC")
      )
      (libsource (lib "声源跟踪小车原理图库") (part "RES"))
    )
    (comp (ref "R82")
      (value "0805_0R_NC")
      (footprint "RES-SMD-0603")
      (description "贴片电阻")
      (fields
        (field (name "BOM_SUPPLIER PART") "C118966")
        (field (name "BOM_MANUFACTURER PART") "3362P-1-104")
        (field (name "CONTRIBUTOR") "LCSC")
      )
      (libsource (lib "声源跟踪小车原理图库") (part "RES"))
    )
    (comp (ref "S1")
      (value "KEY-B-2P")
      (footprint "KEY-TH-B-2P")
      (description "按键开关B")
      (fields (field (name "MANUFACTURER") "C&K") (field (name "MANUFACTURER PART") "PTS645VL83LFS"))
      (libsource (lib "声源跟踪小车原理图库") (part "KEY-B-2P"))
    )
    (comp (ref "TP5")
      (value "TP")
      (footprint "TP")
      (description "TP测试点")
      (libsource (lib "声源跟踪小车原理图库") (part "TP"))
    )
    (comp (ref "TP6")
      (value "TP")
      (footprint "TP")
      (description "TP测试点")
      (libsource (lib "声源跟踪小车原理图库") (part "TP"))
    )
    (comp (ref "U6")
      (value "LMV358")
      (footprint "SOIC-8-LP5.5-P1.27")
      (description "运放IC OPAMP GP 2 CIRCUIT 8SOIC")
      (libsource (lib "声源跟踪小车原理图库") (part "LMV358"))
    )
    (comp (ref "U7")
      (value "STC12C5204AD-35I-SOP20")
      (footprint "SOP-20")
      (fields (field (name "MANUFACTURER") "STC(宏晶)"))
      (libsource (lib "声源跟踪小车原理图库") (part "STC12C5204AD-35I-SOP20"))
    )
    (comp (ref "U8")
      (value "CH340N")
      (footprint "SOP-8-LP5.3-P1.27")
      (fields (field (name "MANUFACTURER") "WCH(南京沁恒)"))
      (libsource (lib "声源跟踪小车原理图库") (part "CH340N"))
    )
    (comp (ref "U9")
      (value "74HC4051PW,118")
      (footprint "TSSOP-16-LP5.7-P0.65")
      (description "复用开关IC MUX/DEMUX 8X1")
      (fields (field (name "MANUFACTURER") "Nexperia(安世)"))
      (libsource (lib "声源跟踪小车原理图库") (part "74HC4051PW,118"))
    )
    (comp (ref "X1")
      (value "11.0592M")
      (footprint "OSC-5032-SMD-2P")
      (description "无源晶振2pin")
      (fields (field (name "MANUFACTURER") "YXC扬兴科技") (field (name "MANUFACTURER PART") "X49SM16MSD2SI"))
      (libsource (lib "声源跟踪小车原理图库") (part "XTAL-2P-WY"))
    )
  )
  (nets
    (net (code "1") (name "/74HC_ADC") (class "Default")
      (node (ref "U7") (pin "14") (pinfunction "P1.2/ADC2/EX_LVD/RST2_14") (pintype "passive"))
      (node (ref "U9") (pin "3") (pinfunction "Z_3") (pintype "passive"))
    )
    (net (code "2") (name "/74HC_EN") (class "Default")
      (node (ref "U7") (pin "15") (pinfunction "P1.3/ADC3_15") (pintype "passive"))
      (node (ref "U9") (pin "6") (pinfunction "E#_6") (pintype "passive"))
    )
    (net (code "3") (name "/D_N") (class "Default")
      (node (ref "U8") (pin "2") (pinfunction "UD-_2") (pintype "passive"))
    )
    (net (code "4") (name "/D_P") (class "Default")
      (node (ref "U8") (pin "1") (pinfunction "UD+_1") (pintype "passive"))
    )
    (net (code "5") (name "/MCU_RXD") (class "Default")
      (node (ref "D15") (pin "2") (pinfunction "A_2") (pintype "passive"))
      (node (ref "P2") (pin "2") (pinfunction "2_2") (pintype "passive"))
      (node (ref "U7") (pin "2") (pinfunction "RXD/P3.0_2") (pintype "passive"))
    )
    (net (code "6") (name "/MCU_TXD") (class "Default")
      (node (ref "D14") (pin "1") (pinfunction "K_1") (pintype "passive"))
      (node (ref "P2") (pin "3") (pinfunction "3_3") (pintype "passive"))
      (node (ref "U7") (pin "3") (pinfunction "TXD/P3.1_3") (pintype "passive"))
    )
    (net (code "7") (name "/Motor_L+") (class "Default")
      (node (ref "R58") (pin "1") (pinfunction "1_1") (pintype "passive"))
      (node (ref "R72") (pin "2") (pinfunction "2_2") (pintype "passive"))
      (node (ref "U7") (pin "8") (pinfunction "CLKOUT0/ECI/T0/P3.4_8") (pintype "passive"))
    )
    (net (code "8") (name "/Motor_L-") (class "Default")
      (node (ref "R59") (pin "2") (pinfunction "2_2") (pintype "passive"))
      (node (ref "R70") (pin "2") (pinfunction "2_2") (pintype "passive"))
      (node (ref "U7") (pin "12") (pinfunction "P1.0/ADC0_12") (pintype "passive"))
    )
    (net (code "9") (name "/Motor_R+") (class "Default")
      (node (ref "R60") (pin "1") (pinfunction "1_1") (pintype "passive"))
      (node (ref "R73") (pin "2") (pinfunction "2_2") (pintype "passive"))
      (node (ref "U7") (pin "9") (pinfunction "CLKOUT1/CCP1/T1/P3.5_9") (pintype "passive"))
    )
    (net (code "10") (name "/Motor_R-") (class "Default")
      (node (ref "R61") (pin "2") (pinfunction "2_2") (pintype "passive"))
      (node (ref "R71") (pin "2") (pinfunction "2_2") (pintype "passive"))
      (node (ref "U7") (pin "13") (pinfunction "P1.1/ADC1_13") (pintype "passive"))
    )
    (net (code "11") (name "/P3_7") (class "Default")
      (node (ref "LED11") (pin "2") (pinfunction "K_2") (pintype "passive"))
      (node (ref "U7") (pin "11") (pinfunction "P3.7/CCP0_11") (pintype "passive"))
    )
    (net (code "12") (name "/REL_V") (class "Default")
      (node (ref "U7") (pin "19") (pinfunction "P1.7/ADC7_19") (pintype "passive"))
    )
    (net (code "13") (name "/RST") (class "Default")
      (node (ref "R78") (pin "2") (pinfunction "2_2") (pintype "passive"))
      (node (ref "U7") (pin "1") (pinfunction "RST_1") (pintype "passive"))
    )
    (net (code "14") (name "/Red_light_L") (class "Default")
      (node (ref "R56") (pin "1") (pinfunction "1_1") (pintype "passive"))
      (node (ref "TP5") (pin "1") (pinfunction "1_1") (pintype "passive"))
      (node (ref "U7") (pin "6") (pinfunction "INT0#/P3.2_6") (pintype "passive"))
    )
    (net (code "15") (name "/Red_light_R") (class "Default")
      (node (ref "R57") (pin "1") (pinfunction "1_1") (pintype "passive"))
      (node (ref "TP6") (pin "1") (pinfunction "1_1") (pintype "passive"))
      (node (ref "U7") (pin "7") (pinfunction "INT1#/P3.3_7") (pintype "passive"))
    )
    (net (code "16") (name "/S0") (class "Default")
      (node (ref "U7") (pin "16") (pinfunction "P1.4/ADC4_16") (pintype "passive"))
      (node (ref "U9") (pin "11") (pinfunction "S0_11") (pintype "passive"))
    )
    (net (code "17") (name "/S1") (class "Default")
      (node (ref "U7") (pin "17") (pinfunction "P1.5/ADC5_17") (pintype "passive"))
      (node (ref "U9") (pin "10") (pinfunction "S1_10") (pintype "passive"))
    )
    (net (code "18") (name "/S2") (class "Default")
      (node (ref "U7") (pin "18") (pinfunction "P1.6/ADC6_18") (pintype "passive"))
      (node (ref "U9") (pin "9") (pinfunction "S2_9") (pintype "passive"))
    )
    (net (code "19") (name "/Signal_1") (class "Default")
      (node (ref "U9") (pin "13") (pinfunction "Y0_13") (pintype "passive"))
    )
    (net (code "20") (name "/Signal_2") (class "Default")
      (node (ref "U9") (pin "14") (pinfunction "Y1_14") (pintype "passive"))
    )
    (net (code "21") (name "/Signal_3") (class "Default")
      (node (ref "U9") (pin "15") (pinfunction "Y2_15") (pintype "passive"))
    )
    (net (code "22") (name "/Signal_4") (class "Default")
      (node (ref "U9") (pin "12") (pinfunction "Y3_12") (pintype "passive"))
    )
    (net (code "23") (name "/X1") (class "Default")
      (node (ref "C70") (pin "2") (pinfunction "2_2") (pintype "passive"))
      (node (ref "R80") (pin "1") (pinfunction "1_1") (pintype "passive"))
      (node (ref "U7") (pin "5") (pinfunction "XTAL1_5") (pintype "passive"))
      (node (ref "X1") (pin "1") (pinfunction "OSC1_1") (pintype "passive"))
    )
    (net (code "24") (name "/X2") (class "Default")
      (node (ref "C71") (pin "2") (pinfunction "2_2") (pintype "passive"))
      (node (ref "R80") (pin "2") (pinfunction "2_2") (pintype "passive"))
      (node (ref "U7") (pin "4") (pinfunction "XTAL2_4") (pintype "passive"))
      (node (ref "X1") (pin "2") (pinfunction "OSC2_2") (pintype "passive"))
    )
    (net (code "25") (name "3.3V") (class "Default")
      (node (ref "C58") (pin "2") (pinfunction "2_2") (pintype "passive"))
      (node (ref "C59") (pin "2") (pinfunction "2_2") (pintype "passive"))
      (node (ref "C60") (pin "2") (pinfunction "2_2") (pintype "passive"))
      (node (ref "C72") (pin "1") (pinfunction "1_1") (pintype "passive"))
      (node (ref "C73") (pin "1") (pinfunction "1_1") (pintype "passive"))
      (node (ref "R46") (pin "1") (pinfunction "1_1") (pintype "passive"))
      (node (ref "R46") (pin "2") (pinfunction "2_2") (pintype "passive"))
      (node (ref "R47") (pin "2") (pinfunction "2_2") (pintype "passive"))
      (node (ref "R48") (pin "1") (pinfunction "1_1") (pintype "passive"))
      (node (ref "R48") (pin "2") (pinfunction "2_2") (pintype "passive"))
      (node (ref "R49") (pin "2") (pinfunction "2_2") (pintype "passive"))
      (node (ref "R54") (pin "2") (pinfunction "2_2") (pintype "passive"))
      (node (ref "R55") (pin "2") (pinfunction "2_2") (pintype "passive"))
      (node (ref "R62") (pin "1") (pinfunction "1_1") (pintype "passive"))
      (node (ref "R64") (pin "1") (pinfunction "1_1") (pintype "passive"))
      (node (ref "U6") (pin "8") (pinfunction "VCC+_8") (pintype "power_in"))
      (node (ref "U9") (pin "16") (pinfunction "VCC_16") (pintype "passive"))
    )
    (net (code "26") (name "5V") (class "Default")
      (node (ref "C64") (pin "2") (pinfunction "2_2") (pintype "passive"))
      (node (ref "C65") (pin "2") (pinfunction "2_2") (pintype "passive"))
      (node (ref "C66") (pin "2") (pinfunction "2_2") (pintype "passive"))
      (node (ref "C67") (pin "2") (pinfunction "2_2") (pintype "passive"))
      (node (ref "P1") (pin "1") (pinfunction "1_1") (pintype "passive"))
      (node (ref "P2") (pin "1") (pinfunction "1_1") (pintype "passive"))
      (node (ref "R81") (pin "1") (pinfunction "1_1") (pintype "passive"))
      (node (ref "S1") (pin "2") (pinfunction "2_2") (pintype "passive"))
      (node (ref "U7") (pin "20") (pinfunction "VCC_20") (pintype "passive"))
    )
    (net (code "27") (name "GND") (class "Default")
      (node (ref "C52") (pin "2") (pinfunction "2_2") (pintype "passive"))
      (node (ref "C53") (pin "1") (pinfunction "1_1") (pintype "passive"))
      (node (ref "C54") (pin "1") (pinfunction "1_1") (pintype "passive"))
      (node (ref "C55") (pin "2") (pinfunction "2_2") (pintype "passive"))
      (node (ref "C56") (pin "1") (pinfunction "1_1") (pintype "passive"))
      (node (ref "C57") (pin "1") (pinfunction "1_1") (pintype "passive"))
      (node (ref "C58") (pin "1") (pinfunction "1_1") (pintype "passive"))
      (node (ref "C63") (pin "2") (pinfunction "2_2") (pintype "passive"))
      (node (ref "C64") (pin "1") (pinfunction "1_1") (pintype "passive"))
      (node (ref "C65") (pin "1") (pinfunction "1_1") (pintype "passive"))
      (node (ref "C66") (pin "1") (pinfunction "1_1") (pintype "passive"))
      (node (ref "C68") (pin "2") (pinfunction "2_2") (pintype "passive"))
      (node (ref "C69") (pin "2") (pinfunction "2_2") (pintype "passive"))
      (node (ref "C70") (pin "1") (pinfunction "1_1") (pintype "passive"))
      (node (ref "C71") (pin "1") (pinfunction "1_1") (pintype "passive"))
      (node (ref "C72") (pin "2") (pinfunction "2_2") (pintype "passive"))
      (node (ref "C73") (pin "2") (pinfunction "2_2") (pintype "passive"))
      (node (ref "D10") (pin "1") (pinfunction "K_1") (pintype "passive"))
      (node (ref "D11") (pin "1") (pinfunction "K_1") (pintype "passive"))
      (node (ref "D12") (pin "1") (pinfunction "K_1") (pintype "passive"))
      (node (ref "D13") (pin "1") (pinfunction "K_1") (pintype "passive"))
      (node (ref "LED10") (pin "2") (pinfunction "K_2") (pintype "passive"))
      (node (ref "LED7") (pin "1") (pinfunction "A_1") (pintype "passive"))
      (node (ref "LED8") (pin "1") (pinfunction "A_1") (pintype "passive"))
      (node (ref "LED9") (pin "2") (pinfunction "K_2") (pintype "passive"))
      (node (ref "P2") (pin "4") (pinfunction "4_4") (pintype "passive"))
      (node (ref "Q10") (pin "2") (pinfunction "E_2") (pintype "passive"))
      (node (ref "Q11") (pin "2") (pinfunction "E_2") (pintype "passive"))
      (node (ref "Q12") (pin "2") (pinfunction "E_2") (pintype "passive"))
      (node (ref "Q13") (pin "2") (pinfunction "E_2") (pintype "passive"))
      (node (ref "Q14") (pin "2") (pinfunction "E_2") (pintype "passive"))
      (node (ref "Q15") (pin "2") (pinfunction "E_2") (pintype "passive"))
      (node (ref "Q16") (pin "2") (pinfunction "E_2") (pintype "passive"))
      (node (ref "Q9") (pin "2") (pinfunction "E_2") (pintype "passive"))
      (node (ref "R63") (pin "1") (pinfunction "1_1") (pintype "passive"))
      (node (ref "R65") (pin "1") (pinfunction "1_1") (pintype "passive"))
      (node (ref "R74") (pin "1") (pinfunction "1_1") (pintype "passive"))
      (node (ref "R75") (pin "1") (pinfunction "1_1") (pintype "passive"))
      (node (ref "R76") (pin "1") (pinfunction "1_1") (pintype "passive"))
      (node (ref "R77") (pin "1") (pinfunction "1_1") (pintype "passive"))
      (node (ref "R79") (pin "1") (pinfunction "1_1") (pintype "passive"))
      (node (ref "R82") (pin "1") (pinfunction "1_1") (pintype "passive"))
      (node (ref "S1") (pin "3") (pinfunction "3_3") (pintype "passive"))
      (node (ref "S1") (pin "4") (pinfunction "4_4") (pintype "passive"))
      (node (ref "U6") (pin "4") (pinfunction "GND_4") (pintype "power_in"))
      (node (ref "U7") (pin "10") (pinfunction "GND_10") (pintype "passive"))
      (node (ref "U8") (pin "3") (pinfunction "GND_3") (pintype "passive"))
      (node (ref "U9") (pin "8") (pinfunction "GND_8") (pintype "passive"))
    )
    (net (code "28") (name "Motor_5V") (class "Default")
      (node (ref "C52") (pin "1") (pinfunction "1_1") (pintype "passive"))
      (node (ref "C53") (pin "2") (pinfunction "2_2") (pintype "passive"))
      (node (ref "C54") (pin "2") (pinfunction "2_2") (pintype "passive"))
      (node (ref "C55") (pin "1") (pinfunction "1_1") (pintype "passive"))
      (node (ref "C56") (pin "2") (pinfunction "2_2") (pintype "passive"))
      (node (ref "C57") (pin "2") (pinfunction "2_2") (pintype "passive"))
      (node (ref "D5") (pin "2") (pinfunction "A_2") (pintype "passive"))
      (node (ref "D6") (pin "2") (pinfunction "A_2") (pintype "passive"))
      (node (ref "D7") (pin "2") (pinfunction "A_2") (pintype "passive"))
      (node (ref "D8") (pin "2") (pinfunction "A_2") (pintype "passive"))
      (node (ref "D9") (pin "2") (pinfunction "A_2") (pintype "passive"))
      (node (ref "Q5") (pin "2") (pinfunction "E_2") (pintype "passive"))
      (node (ref "Q6") (pin "2") (pinfunction "E_2") (pintype "passive"))
      (node (ref "Q7") (pin "2") (pinfunction "E_2") (pintype "passive"))
      (node (ref "Q8") (pin "2") (pinfunction "E_2") (pintype "passive"))
      (node (ref "R50") (pin "2") (pinfunction "2_2") (pintype "passive"))
      (node (ref "R51") (pin "2") (pinfunction "2_2") (pintype "passive"))
      (node (ref "R52") (pin "2") (pinfunction "2_2") (pintype "passive"))
      (node (ref "R53") (pin "2") (pinfunction "2_2") (pintype "passive"))
      (node (ref "R66") (pin "2") (pinfunction "2_2") (pintype "passive"))
      (node (ref "R67") (pin "2") (pinfunction "2_2") (pintype "passive"))
      (node (ref "R68") (pin "2") (pinfunction "2_2") (pintype "passive"))
      (node (ref "R69") (pin "2") (pinfunction "2_2") (pintype "passive"))
    )
    (net (code "29") (name "Net-(C67-Pad1)") (class "Default")
      (node (ref "C67") (pin "1") (pinfunction "1_1") (pintype "passive"))
      (node (ref "R78") (pin "1") (pinfunction "1_1") (pintype "passive"))
      (node (ref "R79") (pin "2") (pinfunction "2_2") (pintype "passive"))
      (node (ref "S1") (pin "1") (pinfunction "1_1") (pintype "passive"))
    )
    (net (code "30") (name "Net-(D5-K)") (class "Default")
      (node (ref "D5") (pin "1") (pinfunction "K_1") (pintype "passive"))
      (node (ref "P1") (pin "2") (pinfunction "2_2") (pintype "passive"))
    )
    (net (code "31") (name "Net-(D10-A)") (class "Default")
      (node (ref "C61") (pin "1") (pinfunction "1_1") (pintype "passive"))
      (node (ref "D10") (pin "2") (pinfunction "A_2") (pintype "passive"))
      (node (ref "D6") (pin "1") (pinfunction "K_1") (pintype "passive"))
      (node (ref "J3") (pin "1") (pinfunction "1_1") (pintype "passive"))
      (node (ref "Q11") (pin "3") (pinfunction "C_3") (pintype "passive"))
      (node (ref "Q7") (pin "3") (pinfunction "C_3") (pintype "passive"))
    )
    (net (code "32") (name "Net-(D11-A)") (class "Default")
      (node (ref "C61") (pin "2") (pinfunction "2_2") (pintype "passive"))
      (node (ref "D11") (pin "2") (pinfunction "A_2") (pintype "passive"))
      (node (ref "D7") (pin "1") (pinfunction "K_1") (pintype "passive"))
      (node (ref "J3") (pin "2") (pinfunction "2_2") (pintype "passive"))
      (node (ref "Q5") (pin "3") (pinfunction "C_3") (pintype "passive"))
      (node (ref "Q9") (pin "3") (pinfunction "C_3") (pintype "passive"))
    )
    (net (code "33") (name "Net-(D12-A)") (class "Default")
      (node (ref "C62") (pin "1") (pinfunction "1_1") (pintype "passive"))
      (node (ref "D12") (pin "2") (pinfunction "A_2") (pintype "passive"))
      (node (ref "D8") (pin "1") (pinfunction "K_1") (pintype "passive"))
      (node (ref "J4") (pin "1") (pinfunction "1_1") (pintype "passive"))
      (node (ref "Q12") (pin "3") (pinfunction "C_3") (pintype "passive"))
      (node (ref "Q8") (pin "3") (pinfunction "C_3") (pintype "passive"))
    )
    (net (code "34") (name "Net-(D13-A)") (class "Default")
      (node (ref "C62") (pin "2") (pinfunction "2_2") (pintype "passive"))
      (node (ref "D13") (pin "2") (pinfunction "A_2") (pintype "passive"))
      (node (ref "D9") (pin "1") (pinfunction "K_1") (pintype "passive"))
      (node (ref "J4") (pin "2") (pinfunction "2_2") (pintype "passive"))
      (node (ref "Q10") (pin "3") (pinfunction "C_3") (pintype "passive"))
      (node (ref "Q6") (pin "3") (pinfunction "C_3") (pintype "passive"))
    )
    (net (code "35") (name "Net-(D14-A)") (class "Default")
      (node (ref "D14") (pin "2") (pinfunction "A_2") (pintype "passive"))
      (node (ref "U8") (pin "7") (pinfunction "RXD_7") (pintype "passive"))
    )
    (net (code "36") (name "Net-(D15-K)") (class "Default")
      (node (ref "D15") (pin "1") (pinfunction "K_1") (pintype "passive"))
      (node (ref "U8") (pin "6") (pinfunction "TXD_6") (pintype "passive"))
    )
    (net (code "37") (name "Net-(LED7-K)") (class "Default")
      (node (ref "C59") (pin "1") (pinfunction "1_1") (pintype "passive"))
      (node (ref "LED7") (pin "2") (pinfunction "K_2") (pintype "passive"))
      (node (ref "R46") (pin "3") (pinfunction "3_3") (pintype "passive"))
      (node (ref "R47") (pin "1") (pinfunction "1_1") (pintype "passive"))
      (node (ref "U6") (pin "3") (pinfunction "1IN+_3") (pintype "tri_state"))
    )
    (net (code "38") (name "Net-(LED8-K)") (class "Default")
      (node (ref "C60") (pin "1") (pinfunction "1_1") (pintype "passive"))
      (node (ref "LED8") (pin "2") (pinfunction "K_2") (pintype "passive"))
      (node (ref "R48") (pin "3") (pinfunction "3_3") (pintype "passive"))
      (node (ref "R49") (pin "1") (pinfunction "1_1") (pintype "passive"))
      (node (ref "U6") (pin "5") (pinfunction "1IN+_5") (pintype "tri_state"))
    )
    (net (code "39") (name "Net-(LED9-A)") (class "Default")
      (node (ref "LED9") (pin "1") (pinfunction "A_1") (pintype "passive"))
      (node (ref "R54") (pin "1") (pinfunction "1_1") (pintype "passive"))
    )
    (net (code "40") (name "Net-(LED10-A)") (class "Default")
      (node (ref "LED10") (pin "1") (pinfunction "A_1") (pintype "passive"))
      (node (ref "R55") (pin "1") (pinfunction "1_1") (pintype "passive"))
    )
    (net (code "41") (name "Net-(LED11-A)") (class "Default")
      (node (ref "LED11") (pin "1") (pinfunction "A_1") (pintype "passive"))
      (node (ref "R81") (pin "2") (pinfunction "2_2") (pintype "passive"))
    )
    (net (code "42") (name "Net-(Q5-B)") (class "Default")
      (node (ref "Q5") (pin "1") (pinfunction "B_1") (pintype "passive"))
      (node (ref "R51") (pin "1") (pinfunction "1_1") (pintype "passive"))
      (node (ref "R59") (pin "1") (pinfunction "1_1") (pintype "passive"))
    )
    (net (code "43") (name "Net-(Q6-B)") (class "Default")
      (node (ref "Q6") (pin "1") (pinfunction "B_1") (pintype "passive"))
      (node (ref "R53") (pin "1") (pinfunction "1_1") (pintype "passive"))
      (node (ref "R61") (pin "1") (pinfunction "1_1") (pintype "passive"))
    )
    (net (code "44") (name "Net-(Q7-B)") (class "Default")
      (node (ref "Q7") (pin "1") (pinfunction "B_1") (pintype "passive"))
      (node (ref "R50") (pin "1") (pinfunction "1_1") (pintype "passive"))
      (node (ref "R58") (pin "2") (pinfunction "2_2") (pintype "passive"))
    )
    (net (code "45") (name "Net-(Q8-B)") (class "Default")
      (node (ref "Q8") (pin "1") (pinfunction "B_1") (pintype "passive"))
      (node (ref "R52") (pin "1") (pinfunction "1_1") (pintype "passive"))
      (node (ref "R60") (pin "2") (pinfunction "2_2") (pintype "passive"))
    )
    (net (code "46") (name "Net-(Q10-B)") (class "Default")
      (node (ref "Q10") (pin "1") (pinfunction "B_1") (pintype "passive"))
      (node (ref "Q14") (pin "3") (pinfunction "C_3") (pintype "passive"))
      (node (ref "R69") (pin "1") (pinfunction "1_1") (pintype "passive"))
    )
    (net (code "47") (name "Net-(Q11-B)") (class "Default")
      (node (ref "Q11") (pin "1") (pinfunction "B_1") (pintype "passive"))
      (node (ref "Q15") (pin "3") (pinfunction "C_3") (pintype "passive"))
      (node (ref "R66") (pin "1") (pinfunction "1_1") (pintype "passive"))
    )
    (net (code "48") (name "Net-(Q12-B)") (class "Default")
      (node (ref "Q12") (pin "1") (pinfunction "B_1") (pintype "passive"))
      (node (ref "Q16") (pin "3") (pinfunction "C_3") (pintype "passive"))
      (node (ref "R68") (pin "1") (pinfunction "1_1") (pintype "passive"))
    )
    (net (code "49") (name "Net-(Q13-B)") (class "Default")
      (node (ref "Q13") (pin "1") (pinfunction "B_1") (pintype "passive"))
      (node (ref "R72") (pin "1") (pinfunction "1_1") (pintype "passive"))
      (node (ref "R76") (pin "2") (pinfunction "2_2") (pintype "passive"))
    )
    (net (code "50") (name "Net-(Q13-C)") (class "Default")
      (node (ref "Q13") (pin "3") (pinfunction "C_3") (pintype "passive"))
      (node (ref "Q9") (pin "1") (pinfunction "B_1") (pintype "passive"))
      (node (ref "R67") (pin "1") (pinfunction "1_1") (pintype "passive"))
    )
    (net (code "51") (name "Net-(Q14-B)") (class "Default")
      (node (ref "Q14") (pin "1") (pinfunction "B_1") (pintype "passive"))
      (node (ref "R73") (pin "1") (pinfunction "1_1") (pintype "passive"))
      (node (ref "R77") (pin "2") (pinfunction "2_2") (pintype "passive"))
    )
    (net (code "52") (name "Net-(Q15-B)") (class "Default")
      (node (ref "Q15") (pin "1") (pinfunction "B_1") (pintype "passive"))
      (node (ref "R70") (pin "1") (pinfunction "1_1") (pintype "passive"))
      (node (ref "R74") (pin "2") (pinfunction "2_2") (pintype "passive"))
    )
    (net (code "53") (name "Net-(Q16-B)") (class "Default")
      (node (ref "Q16") (pin "1") (pinfunction "B_1") (pintype "passive"))
      (node (ref "R71") (pin "1") (pinfunction "1_1") (pintype "passive"))
      (node (ref "R75") (pin "2") (pinfunction "2_2") (pintype "passive"))
    )
    (net (code "54") (name "Net-(U6A-1IN-)") (class "Default")
      (node (ref "R62") (pin "2") (pinfunction "2_2") (pintype "passive"))
      (node (ref "R63") (pin "2") (pinfunction "2_2") (pintype "passive"))
      (node (ref "U6") (pin "2") (pinfunction "1IN-_2") (pintype "tri_state"))
    )
    (net (code "55") (name "Net-(U6A-OUT)") (class "Default")
      (node (ref "R56") (pin "2") (pinfunction "2_2") (pintype "passive"))
      (node (ref "U6") (pin "1") (pinfunction "OUT_1") (pintype "output"))
    )
    (net (code "56") (name "Net-(U6B-1IN-)") (class "Default")
      (node (ref "R64") (pin "2") (pinfunction "2_2") (pintype "passive"))
      (node (ref "R65") (pin "2") (pinfunction "2_2") (pintype "passive"))
      (node (ref "U6") (pin "6") (pinfunction "1IN-_6") (pintype "tri_state"))
    )
    (net (code "57") (name "Net-(U6B-OUT)") (class "Default")
      (node (ref "R57") (pin "2") (pinfunction "2_2") (pintype "passive"))
      (node (ref "U6") (pin "7") (pinfunction "OUT_7") (pintype "output"))
    )
    (net (code "58") (name "Net-(U8-V3)") (class "Default")
      (node (ref "C63") (pin "1") (pinfunction "1_1") (pintype "passive"))
      (node (ref "U8") (pin "8") (pinfunction "V3_8") (pintype "passive"))
    )
    (net (code "59") (name "Net-(U9-VEE)") (class "Default")
      (node (ref "R82") (pin "2") (pinfunction "2_2") (pintype "passive"))
      (node (ref "U9") (pin "7") (pinfunction "VEE_7") (pintype "passive"))
    )
    (net (code "60") (name "VBUS") (class "Default")
      (node (ref "C68") (pin "1") (pinfunction "1_1") (pintype "passive"))
      (node (ref "C69") (pin "1") (pinfunction "1_1") (pintype "passive"))
      (node (ref "U8") (pin "5") (pinfunction "VCC_5") (pintype "passive"))
    )
    (net (code "61") (name "unconnected-(U8-RTS#-Pad4)") (class "Default")
      (node (ref "U8") (pin "4") (pinfunction "RTS#_4") (pintype "passive+no_connect"))
    )
    (net (code "62") (name "unconnected-(U9-Y4-Pad1)") (class "Default")
      (node (ref "U9") (pin "1") (pinfunction "Y4_1") (pintype "passive+no_connect"))
    )
    (net (code "63") (name "unconnected-(U9-Y5-Pad5)") (class "Default")
      (node (ref "U9") (pin "5") (pinfunction "Y5_5") (pintype "passive+no_connect"))
    )
    (net (code "64") (name "unconnected-(U9-Y6-Pad2)") (class "Default")
      (node (ref "U9") (pin "2") (pinfunction "Y6_2") (pintype "passive+no_connect"))
    )
    (net (code "65") (name "unconnected-(U9-Y7-Pad4)") (class "Default")
      (node (ref "U9") (pin "4") (pinfunction "Y7_4") (pintype "passive+no_connect"))
    )
  )
)
